# 2_MCU.net
KiCad netlist of a schematic drawn in Altium Designer
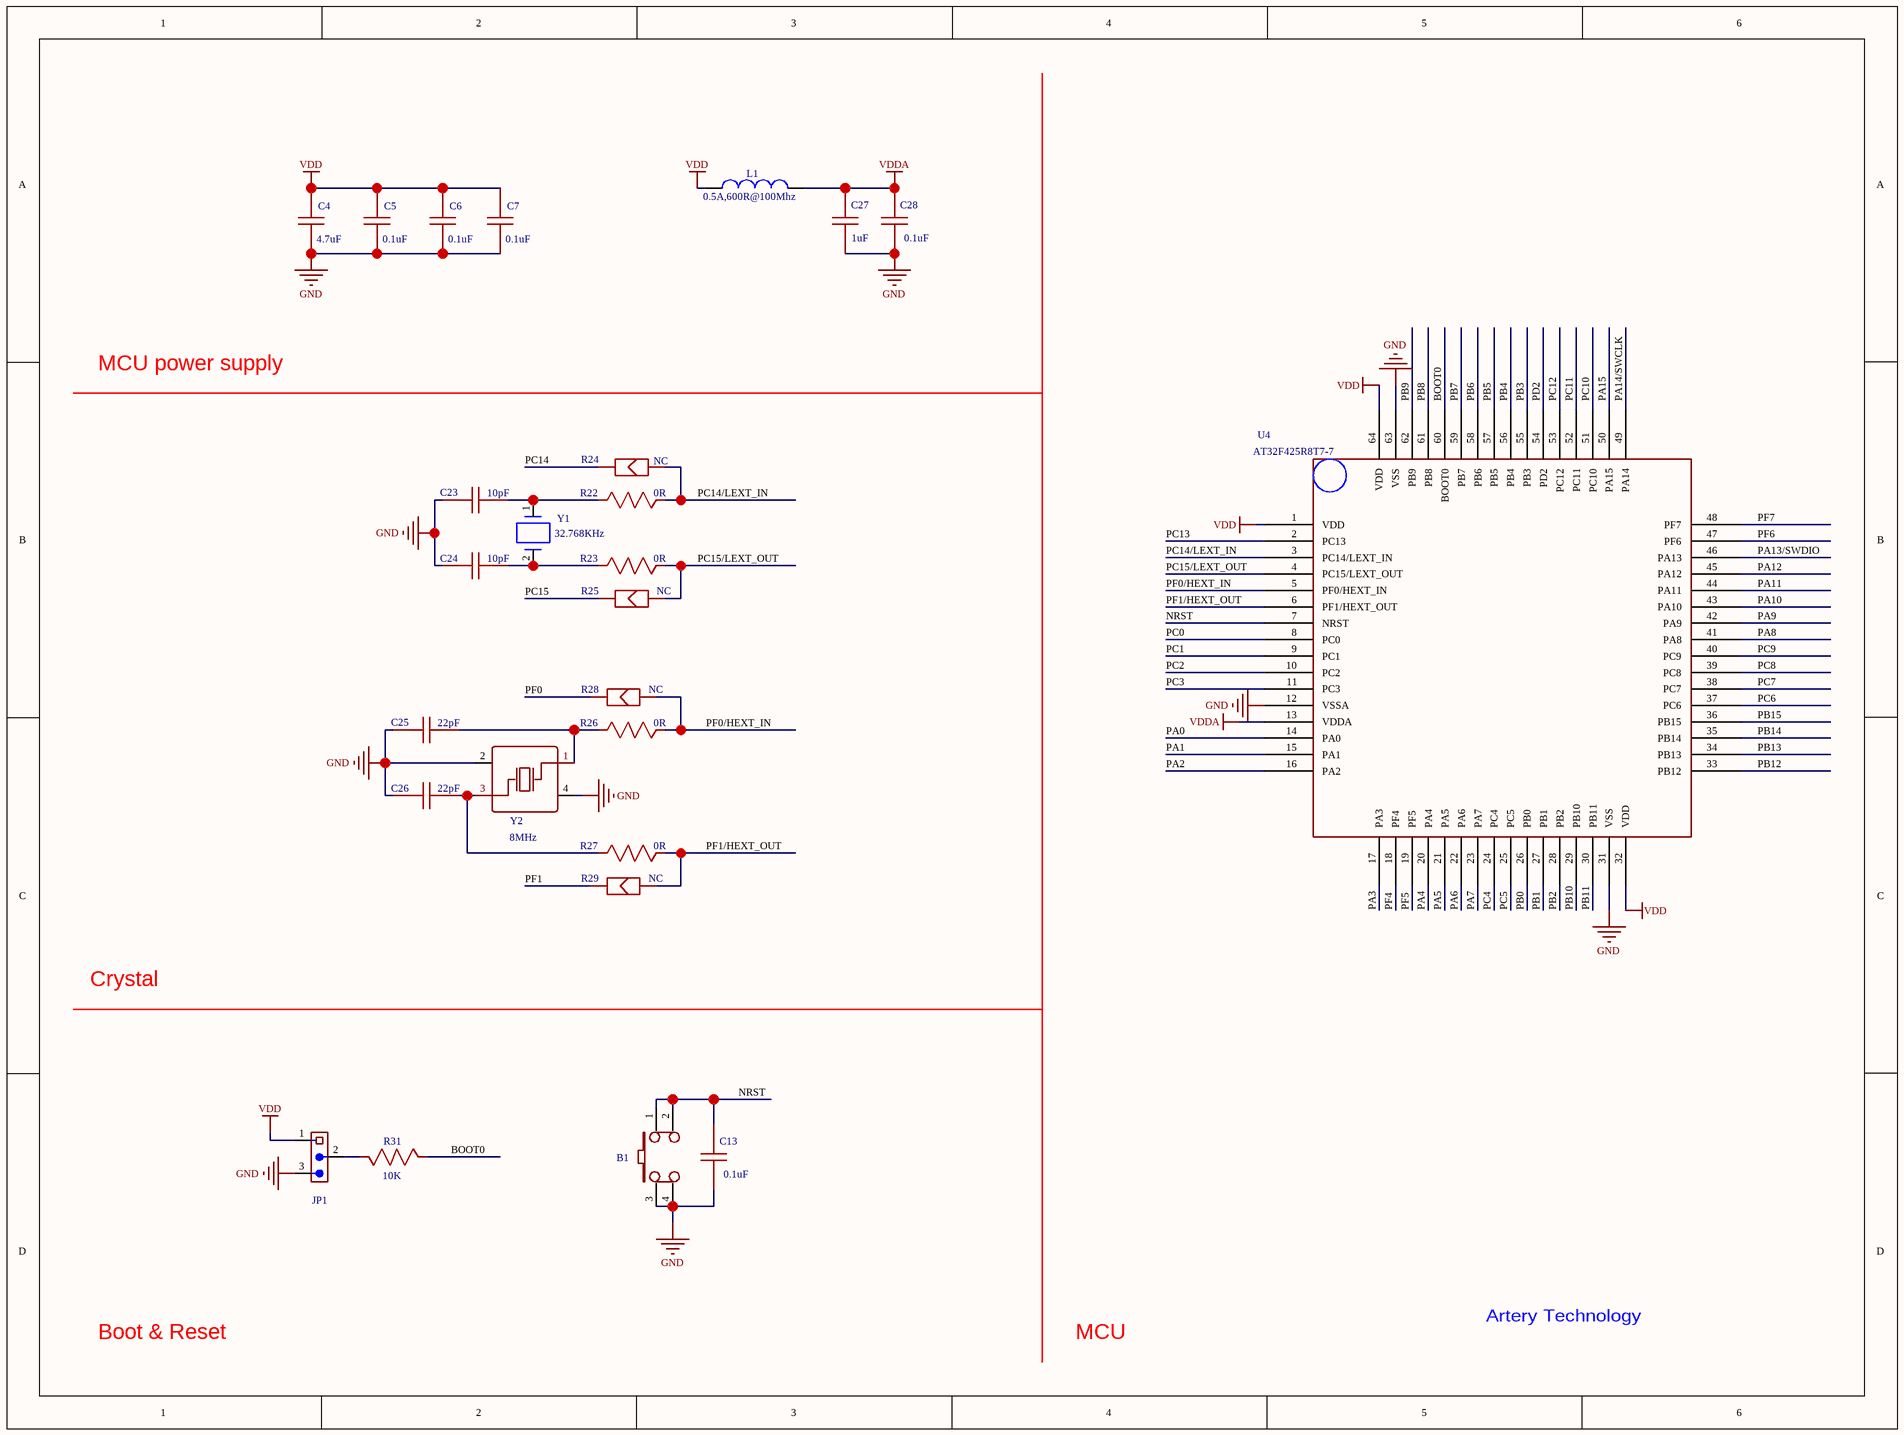
[diagram p0: 2_MCU.schdoc]

(export (version "E")
  (design (tool "Eeschema 10.0.6"))
  (components
    (comp (ref "B1")
      (value "BUTTON_SMT,6.0x6.0x4.5mm")
      (fields (field (name "CONTRIBUTOR") "twb17"))
      (libsource (lib "altium-import") (part "root_1_BUTTON_SMT,6.0x6.0x4.5mm_"))
    )
    (comp (ref "C4")
      (value "4.7uF")
      (fields (field (name "CONTRIBUTOR") "LCEDA_Lib"))
      (libsource (lib "altium-import") (part "root_3_4.7uF_"))
    )
    (comp (ref "C5")
      (value "0.1uF")
      (fields (field (name "CONTRIBUTOR") "LCEDA_Lib"))
      (libsource (lib "altium-import") (part "root_3_0.1uF_"))
    )
    (comp (ref "C6")
      (value "0.1uF")
      (fields (field (name "CONTRIBUTOR") "LCEDA_Lib"))
      (libsource (lib "altium-import") (part "root_3_0.1uF_"))
    )
    (comp (ref "C7")
      (value "0.1uF")
      (fields (field (name "CONTRIBUTOR") "LCEDA_Lib"))
      (libsource (lib "altium-import") (part "root_3_0.1uF_"))
    )
    (comp (ref "C13")
      (value "0.1uF")
      (fields (field (name "CONTRIBUTOR") "LCEDA_Lib"))
      (libsource (lib "altium-import") (part "root_1_0.1uF_"))
    )
    (comp (ref "C23")
      (value "10pF")
      (fields (field (name "CONTRIBUTOR") "LCEDA_Lib"))
      (libsource (lib "altium-import") (part "root_0_10pF_"))
    )
    (comp (ref "C24")
      (value "10pF")
      (fields (field (name "CONTRIBUTOR") "LCEDA_Lib"))
      (libsource (lib "altium-import") (part "root_0_10pF_"))
    )
    (comp (ref "C25")
      (value "22pF")
      (fields (field (name "CONTRIBUTOR") "LCEDA_Lib"))
      (libsource (lib "altium-import") (part "root_0_22pF_"))
    )
    (comp (ref "C26")
      (value "22pF")
      (fields (field (name "CONTRIBUTOR") "LCEDA_Lib"))
      (libsource (lib "altium-import") (part "root_0_22pF_"))
    )
    (comp (ref "C27")
      (value "1uF")
      (fields (field (name "CONTRIBUTOR") "LCEDA_Lib"))
      (libsource (lib "altium-import") (part "root_1_1uF_"))
    )
    (comp (ref "C28")
      (value "0.1uF")
      (fields (field (name "CONTRIBUTOR") "LCEDA_Lib"))
      (libsource (lib "altium-import") (part "root_1_0.1uF_"))
    )
    (comp (ref "JP1") (value "Header 1x3") (libsource (lib "altium-import") (part "root_2_Header 1x3_")))
    (comp (ref "L1")
      (value "0.5A,600R@100Mhz")
      (fields (field (name "CONTRIBUTOR") "twb17"))
      (libsource (lib "altium-import") (part "root_0_0.5A,600R@100Mhz_"))
    )
    (comp (ref "R22")
      (value "0R")
      (fields (field (name "CONTRIBUTOR") "LCEDA_Lib"))
      (libsource (lib "altium-import") (part "root_2_0R_"))
    )
    (comp (ref "R23")
      (value "0R")
      (fields (field (name "CONTRIBUTOR") "LCEDA_Lib"))
      (libsource (lib "altium-import") (part "root_2_0R_"))
    )
    (comp (ref "R24")
      (value "NC")
      (fields (field (name "CONTRIBUTOR") "twb17"))
      (libsource (lib "altium-import") (part "root_2_NC_"))
    )
    (comp (ref "R25")
      (value "NC")
      (fields (field (name "CONTRIBUTOR") "twb17"))
      (libsource (lib "altium-import") (part "root_2_NC_"))
    )
    (comp (ref "R26")
      (value "0R")
      (fields (field (name "CONTRIBUTOR") "LCEDA_Lib"))
      (libsource (lib "altium-import") (part "root_2_0R_"))
    )
    (comp (ref "R27")
      (value "0R")
      (fields (field (name "CONTRIBUTOR") "LCEDA_Lib"))
      (libsource (lib "altium-import") (part "root_2_0R_"))
    )
    (comp (ref "R28")
      (value "NC")
      (fields (field (name "CONTRIBUTOR") "twb17"))
      (libsource (lib "altium-import") (part "root_2_NC_"))
    )
    (comp (ref "R29")
      (value "NC")
      (fields (field (name "CONTRIBUTOR") "twb17"))
      (libsource (lib "altium-import") (part "root_2_NC_"))
    )
    (comp (ref "R31")
      (value "10K")
      (fields (field (name "CONTRIBUTOR") "LCEDA_Lib"))
      (libsource (lib "altium-import") (part "root_0_10K_"))
    )
    (comp (ref "U4")
      (value "AT32F425R8T7-7")
      (fields (field (name "CONTRIBUTOR") "twb17"))
      (libsource (lib "altium-import") (part "root_0_AT32F425R8T7-7_"))
    )
    (comp (ref "Y1")
      (value "32.768KHz")
      (fields (field (name "CONTRIBUTOR") "twb17"))
      (libsource (lib "altium-import") (part "root_1_32.768KHz_"))
    )
    (comp (ref "Y2")
      (value "8MHz")
      (fields
        (field (name "BOM_MANUFACTURER PART") "X50328MSD4SC")
        (field (name "BOM_SUPPLIER PART") "C16422")
      )
      (libsource (lib "altium-import") (part "root_2_8MHz_"))
    )
  )
  (nets
    (net (code "1") (name "/BOOT0") (class "Default")
      (node (ref "R31") (pin "2") (pinfunction "2_2") (pintype "passive"))
      (node (ref "U4") (pin "60") (pinfunction "BOOT0_60") (pintype "passive"))
    )
    (net (code "2") (name "/NRST") (class "Default")
      (node (ref "B1") (pin "1") (pinfunction "1_1") (pintype "passive"))
      (node (ref "B1") (pin "2") (pinfunction "2_2") (pintype "passive"))
      (node (ref "C13") (pin "2") (pinfunction "2_2") (pintype "passive"))
      (node (ref "U4") (pin "7") (pinfunction "NRST_7") (pintype "passive"))
    )
    (net (code "3") (name "/PA0") (class "Default")
      (node (ref "U4") (pin "14") (pinfunction "PA0_14") (pintype "passive"))
    )
    (net (code "4") (name "/PA1") (class "Default")
      (node (ref "U4") (pin "15") (pinfunction "PA1_15") (pintype "passive"))
    )
    (net (code "5") (name "/PA2") (class "Default")
      (node (ref "U4") (pin "16") (pinfunction "PA2_16") (pintype "passive"))
    )
    (net (code "6") (name "/PA3") (class "Default")
      (node (ref "U4") (pin "17") (pinfunction "PA3_17") (pintype "passive"))
    )
    (net (code "7") (name "/PA4") (class "Default")
      (node (ref "U4") (pin "20") (pinfunction "PA4_20") (pintype "passive"))
    )
    (net (code "8") (name "/PA5") (class "Default")
      (node (ref "U4") (pin "21") (pinfunction "PA5_21") (pintype "passive"))
    )
    (net (code "9") (name "/PA6") (class "Default")
      (node (ref "U4") (pin "22") (pinfunction "PA6_22") (pintype "passive"))
    )
    (net (code "10") (name "/PA7") (class "Default")
      (node (ref "U4") (pin "23") (pinfunction "PA7_23") (pintype "passive"))
    )
    (net (code "11") (name "/PA8") (class "Default")
      (node (ref "U4") (pin "41") (pinfunction "PA8_41") (pintype "passive"))
    )
    (net (code "12") (name "/PA9") (class "Default")
      (node (ref "U4") (pin "42") (pinfunction "PA9_42") (pintype "passive"))
    )
    (net (code "13") (name "/PA10") (class "Default")
      (node (ref "U4") (pin "43") (pinfunction "PA10_43") (pintype "passive"))
    )
    (net (code "14") (name "/PA11") (class "Default")
      (node (ref "U4") (pin "44") (pinfunction "PA11_44") (pintype "passive"))
    )
    (net (code "15") (name "/PA12") (class "Default")
      (node (ref "U4") (pin "45") (pinfunction "PA12_45") (pintype "passive"))
    )
    (net (code "16") (name "/PA13{slash}SWDIO") (class "Default")
      (node (ref "U4") (pin "46") (pinfunction "PA13_46") (pintype "passive"))
    )
    (net (code "17") (name "/PA14{slash}SWCLK") (class "Default")
      (node (ref "U4") (pin "49") (pinfunction "PA14_49") (pintype "passive"))
    )
    (net (code "18") (name "/PA15") (class "Default")
      (node (ref "U4") (pin "50") (pinfunction "PA15_50") (pintype "passive"))
    )
    (net (code "19") (name "/PB0") (class "Default")
      (node (ref "U4") (pin "26") (pinfunction "PB0_26") (pintype "passive"))
    )
    (net (code "20") (name "/PB1") (class "Default")
      (node (ref "U4") (pin "27") (pinfunction "PB1_27") (pintype "passive"))
    )
    (net (code "21") (name "/PB2") (class "Default")
      (node (ref "U4") (pin "28") (pinfunction "PB2_28") (pintype "passive"))
    )
    (net (code "22") (name "/PB3") (class "Default")
      (node (ref "U4") (pin "55") (pinfunction "PB3_55") (pintype "passive"))
    )
    (net (code "23") (name "/PB4") (class "Default")
      (node (ref "U4") (pin "56") (pinfunction "PB4_56") (pintype "passive"))
    )
    (net (code "24") (name "/PB5") (class "Default")
      (node (ref "U4") (pin "57") (pinfunction "PB5_57") (pintype "passive"))
    )
    (net (code "25") (name "/PB6") (class "Default")
      (node (ref "U4") (pin "58") (pinfunction "PB6_58") (pintype "passive"))
    )
    (net (code "26") (name "/PB7") (class "Default")
      (node (ref "U4") (pin "59") (pinfunction "PB7_59") (pintype "passive"))
    )
    (net (code "27") (name "/PB8") (class "Default")
      (node (ref "U4") (pin "61") (pinfunction "PB8_61") (pintype "passive"))
    )
    (net (code "28") (name "/PB9") (class "Default")
      (node (ref "U4") (pin "62") (pinfunction "PB9_62") (pintype "passive"))
    )
    (net (code "29") (name "/PB10") (class "Default")
      (node (ref "U4") (pin "29") (pinfunction "PB10_29") (pintype "passive"))
    )
    (net (code "30") (name "/PB11") (class "Default")
      (node (ref "U4") (pin "30") (pinfunction "PB11_30") (pintype "passive"))
    )
    (net (code "31") (name "/PB12") (class "Default")
      (node (ref "U4") (pin "33") (pinfunction "PB12_33") (pintype "passive"))
    )
    (net (code "32") (name "/PB13") (class "Default")
      (node (ref "U4") (pin "34") (pinfunction "PB13_34") (pintype "passive"))
    )
    (net (code "33") (name "/PB14") (class "Default")
      (node (ref "U4") (pin "35") (pinfunction "PB14_35") (pintype "passive"))
    )
    (net (code "34") (name "/PB15") (class "Default")
      (node (ref "U4") (pin "36") (pinfunction "PB15_36") (pintype "passive"))
    )
    (net (code "35") (name "/PC0") (class "Default")
      (node (ref "U4") (pin "8") (pinfunction "PC0_8") (pintype "passive"))
    )
    (net (code "36") (name "/PC1") (class "Default")
      (node (ref "U4") (pin "9") (pinfunction "PC1_9") (pintype "passive"))
    )
    (net (code "37") (name "/PC2") (class "Default")
      (node (ref "U4") (pin "10") (pinfunction "PC2_10") (pintype "passive"))
    )
    (net (code "38") (name "/PC3") (class "Default")
      (node (ref "U4") (pin "11") (pinfunction "PC3_11") (pintype "passive"))
    )
    (net (code "39") (name "/PC4") (class "Default")
      (node (ref "U4") (pin "24") (pinfunction "PC4_24") (pintype "passive"))
    )
    (net (code "40") (name "/PC5") (class "Default")
      (node (ref "U4") (pin "25") (pinfunction "PC5_25") (pintype "passive"))
    )
    (net (code "41") (name "/PC6") (class "Default")
      (node (ref "U4") (pin "37") (pinfunction "PC6_37") (pintype "passive"))
    )
    (net (code "42") (name "/PC7") (class "Default")
      (node (ref "U4") (pin "38") (pinfunction "PC7_38") (pintype "passive"))
    )
    (net (code "43") (name "/PC8") (class "Default")
      (node (ref "U4") (pin "39") (pinfunction "PC8_39") (pintype "passive"))
    )
    (net (code "44") (name "/PC9") (class "Default")
      (node (ref "U4") (pin "40") (pinfunction "PC9_40") (pintype "passive"))
    )
    (net (code "45") (name "/PC10") (class "Default")
      (node (ref "U4") (pin "51") (pinfunction "PC10_51") (pintype "passive"))
    )
    (net (code "46") (name "/PC11") (class "Default")
      (node (ref "U4") (pin "52") (pinfunction "PC11_52") (pintype "passive"))
    )
    (net (code "47") (name "/PC12") (class "Default")
      (node (ref "U4") (pin "53") (pinfunction "PC12_53") (pintype "passive"))
    )
    (net (code "48") (name "/PC13") (class "Default")
      (node (ref "U4") (pin "2") (pinfunction "PC13_2") (pintype "passive"))
    )
    (net (code "49") (name "/PC14") (class "Default")
      (node (ref "R24") (pin "2") (pinfunction "2_2") (pintype "passive"))
    )
    (net (code "50") (name "/PC14{slash}LEXT_IN") (class "Default")
      (node (ref "R22") (pin "1") (pinfunction "1_1") (pintype "passive"))
      (node (ref "R24") (pin "1") (pinfunction "1_1") (pintype "passive"))
      (node (ref "U4") (pin "3") (pinfunction "PC14/LEXT_IN_3") (pintype "passive"))
    )
    (net (code "51") (name "/PC15") (class "Default")
      (node (ref "R25") (pin "2") (pinfunction "2_2") (pintype "passive"))
    )
    (net (code "52") (name "/PC15{slash}LEXT_OUT") (class "Default")
      (node (ref "R23") (pin "1") (pinfunction "1_1") (pintype "passive"))
      (node (ref "R25") (pin "1") (pinfunction "1_1") (pintype "passive"))
      (node (ref "U4") (pin "4") (pinfunction "PC15/LEXT_OUT_4") (pintype "passive"))
    )
    (net (code "53") (name "/PD2") (class "Default")
      (node (ref "U4") (pin "54") (pinfunction "PD2_54") (pintype "passive"))
    )
    (net (code "54") (name "/PF0") (class "Default")
      (node (ref "R28") (pin "2") (pinfunction "2_2") (pintype "passive"))
    )
    (net (code "55") (name "/PF0{slash}HEXT_IN") (class "Default")
      (node (ref "R26") (pin "1") (pinfunction "1_1") (pintype "passive"))
      (node (ref "R28") (pin "1") (pinfunction "1_1") (pintype "passive"))
      (node (ref "U4") (pin "5") (pinfunction "PF0/HEXT_IN_5") (pintype "passive"))
    )
    (net (code "56") (name "/PF1") (class "Default")
      (node (ref "R29") (pin "2") (pinfunction "2_2") (pintype "passive"))
    )
    (net (code "57") (name "/PF1{slash}HEXT_OUT") (class "Default")
      (node (ref "R27") (pin "1") (pinfunction "1_1") (pintype "passive"))
      (node (ref "R29") (pin "1") (pinfunction "1_1") (pintype "passive"))
      (node (ref "U4") (pin "6") (pinfunction "PF1/HEXT_OUT_6") (pintype "passive"))
    )
    (net (code "58") (name "/PF4") (class "Default")
      (node (ref "U4") (pin "18") (pinfunction "PF4_18") (pintype "passive"))
    )
    (net (code "59") (name "/PF5") (class "Default")
      (node (ref "U4") (pin "19") (pinfunction "PF5_19") (pintype "passive"))
    )
    (net (code "60") (name "/PF6") (class "Default")
      (node (ref "U4") (pin "47") (pinfunction "PF6_47") (pintype "passive"))
    )
    (net (code "61") (name "/PF7") (class "Default")
      (node (ref "U4") (pin "48") (pinfunction "PF7_48") (pintype "passive"))
    )
    (net (code "62") (name "GND") (class "Default")
      (node (ref "B1") (pin "3") (pinfunction "3_3") (pintype "passive"))
      (node (ref "B1") (pin "4") (pinfunction "4_4") (pintype "passive"))
      (node (ref "C13") (pin "1") (pinfunction "1_1") (pintype "passive"))
      (node (ref "C23") (pin "1") (pinfunction "1_1") (pintype "passive"))
      (node (ref "C24") (pin "1") (pinfunction "1_1") (pintype "passive"))
      (node (ref "C25") (pin "1") (pinfunction "1_1") (pintype "passive"))
      (node (ref "C26") (pin "1") (pinfunction "1_1") (pintype "passive"))
      (node (ref "C27") (pin "1") (pinfunction "1_1") (pintype "passive"))
      (node (ref "C28") (pin "1") (pinfunction "1_1") (pintype "passive"))
      (node (ref "C4") (pin "2") (pinfunction "2_2") (pintype "passive"))
      (node (ref "C5") (pin "2") (pinfunction "2_2") (pintype "passive"))
      (node (ref "C6") (pin "2") (pinfunction "2_2") (pintype "passive"))
      (node (ref "C7") (pin "2") (pinfunction "2_2") (pintype "passive"))
      (node (ref "JP1") (pin "3") (pinfunction "3_3") (pintype "passive"))
      (node (ref "U4") (pin "12") (pinfunction "VSSA_12") (pintype "passive"))
      (node (ref "U4") (pin "31") (pinfunction "VSS_31") (pintype "passive"))
      (node (ref "U4") (pin "63") (pinfunction "VSS_63") (pintype "passive"))
      (node (ref "Y2") (pin "2") (pinfunction "GND_2") (pintype "passive"))
      (node (ref "Y2") (pin "4") (pinfunction "GND_4") (pintype "passive"))
    )
    (net (code "63") (name "Net-(C23-Pad2)") (class "Default")
      (node (ref "C23") (pin "2") (pinfunction "2_2") (pintype "passive"))
      (node (ref "R22") (pin "2") (pinfunction "2_2") (pintype "passive"))
      (node (ref "Y1") (pin "1") (pinfunction "1_1") (pintype "passive"))
    )
    (net (code "64") (name "Net-(C24-Pad2)") (class "Default")
      (node (ref "C24") (pin "2") (pinfunction "2_2") (pintype "passive"))
      (node (ref "R23") (pin "2") (pinfunction "2_2") (pintype "passive"))
      (node (ref "Y1") (pin "2") (pinfunction "2_2") (pintype "passive"))
    )
    (net (code "65") (name "Net-(JP1-Pad2)") (class "Default")
      (node (ref "JP1") (pin "2") (pinfunction "2_2") (pintype "passive"))
      (node (ref "R31") (pin "1") (pinfunction "1_1") (pintype "passive"))
    )
    (net (code "66") (name "Net-(Y2-OSC1)") (class "Default")
      (node (ref "C25") (pin "2") (pinfunction "2_2") (pintype "passive"))
      (node (ref "R26") (pin "2") (pinfunction "2_2") (pintype "passive"))
      (node (ref "Y2") (pin "1") (pinfunction "OSC1_1") (pintype "passive"))
    )
    (net (code "67") (name "Net-(Y2-OSC2)") (class "Default")
      (node (ref "C26") (pin "2") (pinfunction "2_2") (pintype "passive"))
      (node (ref "R27") (pin "2") (pinfunction "2_2") (pintype "passive"))
      (node (ref "Y2") (pin "3") (pinfunction "OSC2_3") (pintype "passive"))
    )
    (net (code "68") (name "VDD") (class "Default")
      (node (ref "C4") (pin "1") (pinfunction "1_1") (pintype "passive"))
      (node (ref "C5") (pin "1") (pinfunction "1_1") (pintype "passive"))
      (node (ref "C6") (pin "1") (pinfunction "1_1") (pintype "passive"))
      (node (ref "C7") (pin "1") (pinfunction "1_1") (pintype "passive"))
      (node (ref "JP1") (pin "1") (pinfunction "1_1") (pintype "passive"))
      (node (ref "L1") (pin "1") (pinfunction "1_1") (pintype "passive"))
      (node (ref "U4") (pin "1") (pinfunction "VDD_1") (pintype "passive"))
      (node (ref "U4") (pin "32") (pinfunction "VDD_32") (pintype "passive"))
      (node (ref "U4") (pin "64") (pinfunction "VDD_64") (pintype "passive"))
    )
    (net (code "69") (name "VDDA") (class "Default")
      (node (ref "C27") (pin "2") (pinfunction "2_2") (pintype "passive"))
      (node (ref "C28") (pin "2") (pinfunction "2_2") (pintype "passive"))
      (node (ref "L1") (pin "2") (pinfunction "2_2") (pintype "passive"))
      (node (ref "U4") (pin "13") (pinfunction "VDDA_13") (pintype "passive"))
    )
  )
)
